# hand_rev_1_2_b.net
KiCad netlist of a schematic drawn in EAGLE
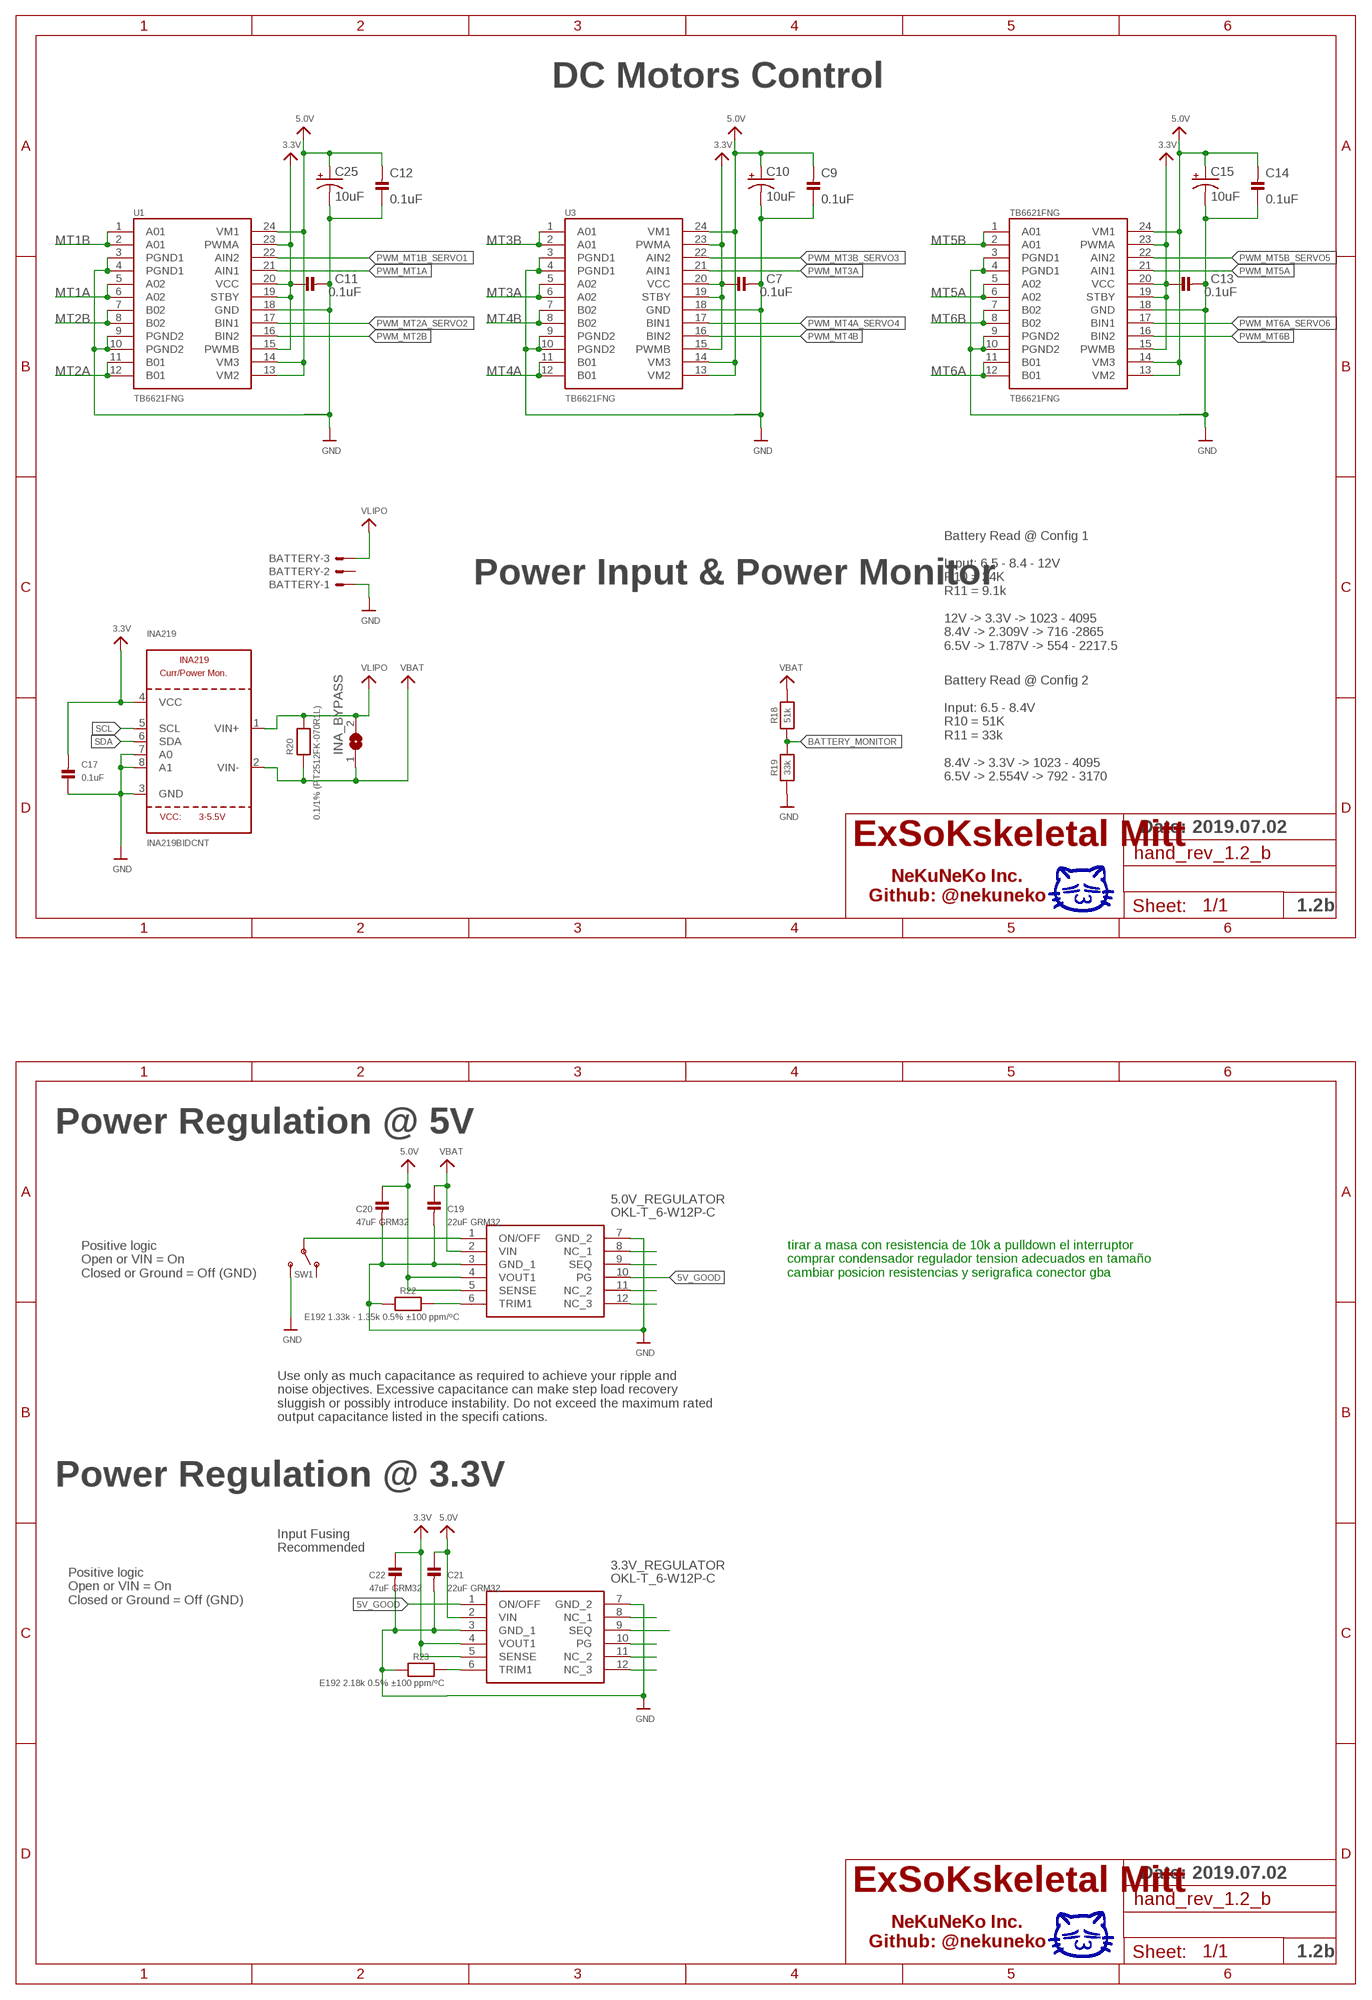
[diagram p0: schematic, sheet 1, part 1 of 2]
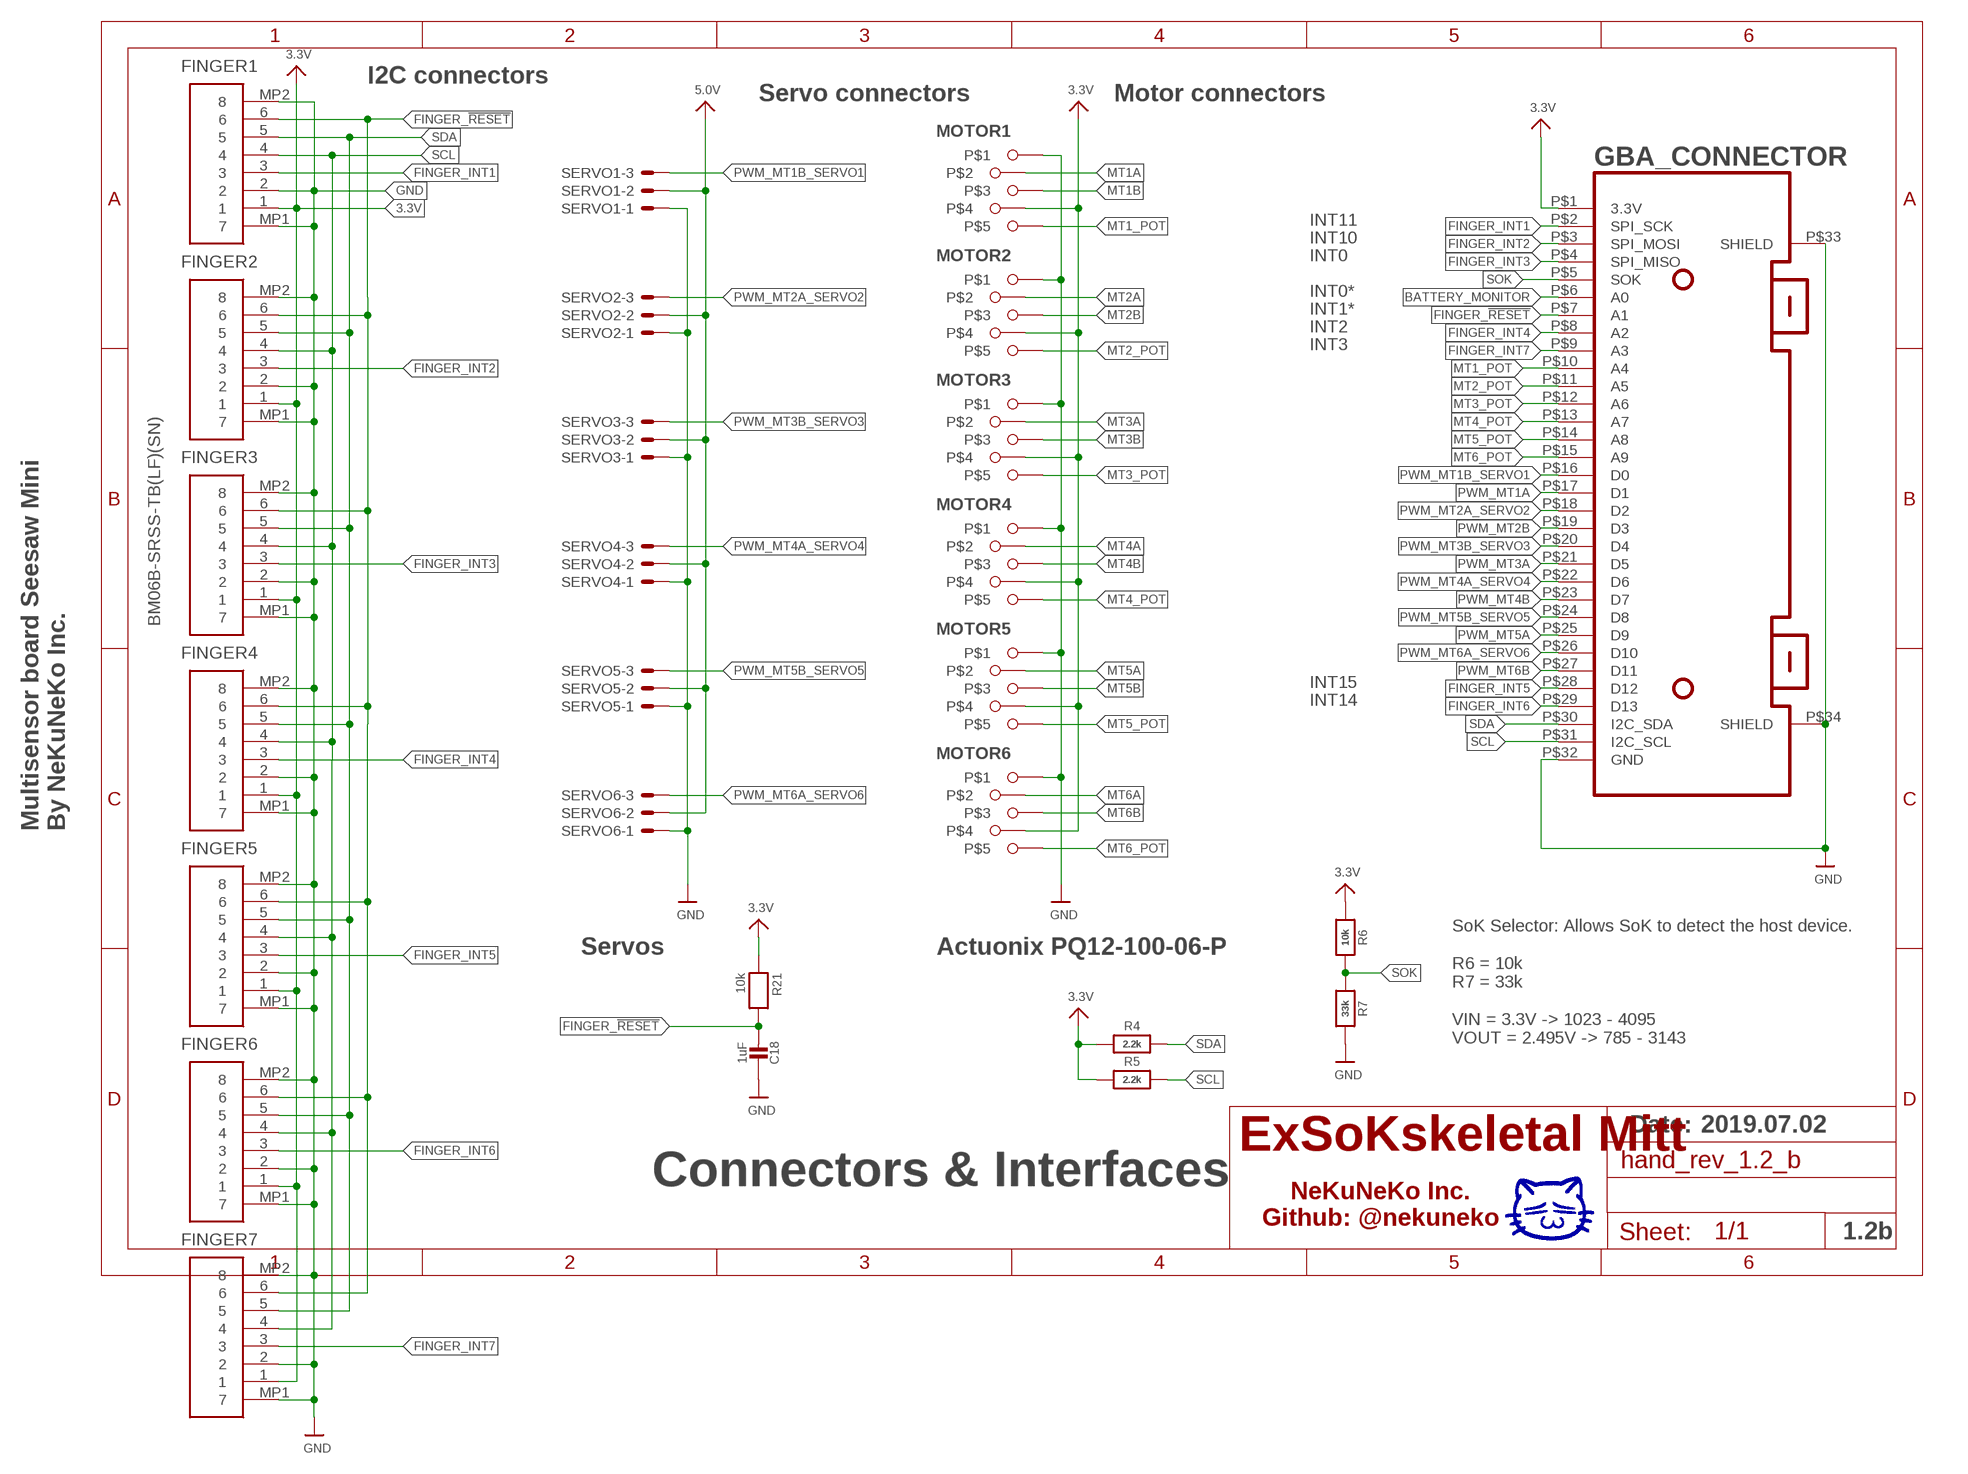
[diagram p1: schematic, sheet 1, part 2 of 2]

(export (version "E")
  (design (tool "Eeschema 10.0.6"))
  (components
    (comp (ref "3.3V_REGULATOR")
      (value "OKL-T_6-W12P-C")
      (footprint "eagle-import:OKL-T3-W12")
      (fields
        (field (name "MANUFACTURER_PART_NUMBER") "OKL-T/6-W12P-C")
        (field (name "MOUSER_PART_NUMBER") "580-OKL-T/6-W12P-C")
      )
      (libsource (lib "eagle-import") (part "OKL-T_6-W12P-C"))
    )
    (comp (ref "5.0V_REGULATOR")
      (value "OKL-T_6-W12P-C")
      (footprint "eagle-import:OKL-T3-W12")
      (fields
        (field (name "MANUFACTURER_PART_NUMBER") "OKL-T/6-W12P-C")
        (field (name "MOUSER_PART_NUMBER") "580-OKL-T/6-W12P-C")
      )
      (libsource (lib "eagle-import") (part "OKL-T_6-W12P-C"))
    )
    (comp (ref "BATTERY")
      (value "JST-XH-03-PIN-LONG-PAD")
      (footprint "eagle-import:JST-XH-03-PACKAGE-LONG-PAD")
      (libsource (lib "eagle-import") (part "JST-XH-03-PIN-LONG-PAD"))
    )
    (comp (ref "C7")
      (value "0.1uF")
      (footprint "eagle-import:_0603")
      (libsource (lib "eagle-import") (part "microbuilder_CAP_CERAMIC_0603"))
    )
    (comp (ref "C9")
      (value "0.1uF")
      (footprint "eagle-import:_0603")
      (libsource (lib "eagle-import") (part "microbuilder_CAP_CERAMIC_0603"))
    )
    (comp (ref "C10")
      (value "10uF")
      (footprint "eagle-import:0603-POLAR")
      (fields (field (name "MPN") "F981A106MMA"))
      (libsource (lib "eagle-import") (part "10UF-POLAR-0603-6.3V-20%(TANT)"))
    )
    (comp (ref "C11")
      (value "0.1uF")
      (footprint "eagle-import:_0603")
      (libsource (lib "eagle-import") (part "microbuilder_CAP_CERAMIC_0603"))
    )
    (comp (ref "C12")
      (value "0.1uF")
      (footprint "eagle-import:_0603")
      (libsource (lib "eagle-import") (part "microbuilder_CAP_CERAMIC_0603"))
    )
    (comp (ref "C13")
      (value "0.1uF")
      (footprint "eagle-import:_0603")
      (libsource (lib "eagle-import") (part "microbuilder_CAP_CERAMIC_0603"))
    )
    (comp (ref "C14")
      (value "0.1uF")
      (footprint "eagle-import:_0603")
      (libsource (lib "eagle-import") (part "microbuilder_CAP_CERAMIC_0603"))
    )
    (comp (ref "C15")
      (value "10uF")
      (footprint "eagle-import:0603-POLAR")
      (fields (field (name "MPN") "F981A106MMA"))
      (libsource (lib "eagle-import") (part "10UF-POLAR-0603-6.3V-20%(TANT)"))
    )
    (comp (ref "C17")
      (value "0.1uF")
      (footprint "eagle-import:_0603")
      (libsource (lib "eagle-import") (part "microbuilder_CAP_CERAMIC_0603"))
    )
    (comp (ref "C18")
      (value "1uF")
      (footprint "eagle-import:MICROBUILDER__0603")
      (libsource (lib "eagle-import") (part "CAP_CERAMIC_0603"))
    )
    (comp (ref "C19")
      (value "22uF GRM32")
      (footprint "eagle-import:1206")
      (libsource (lib "eagle-import") (part "CAP_CERAMIC1206"))
    )
    (comp (ref "C20")
      (value "47uF GRM32")
      (footprint "eagle-import:1206")
      (libsource (lib "eagle-import") (part "CAP_CERAMIC1206"))
    )
    (comp (ref "C21")
      (value "22uF GRM32")
      (footprint "eagle-import:1206")
      (libsource (lib "eagle-import") (part "CAP_CERAMIC1206"))
    )
    (comp (ref "C22")
      (value "47uF GRM32")
      (footprint "eagle-import:1206")
      (libsource (lib "eagle-import") (part "CAP_CERAMIC1206"))
    )
    (comp (ref "C25")
      (value "10uF")
      (footprint "eagle-import:0603-POLAR")
      (fields (field (name "MPN") "F981A106MMA"))
      (libsource (lib "eagle-import") (part "10UF-POLAR-0603-6.3V-20%(TANT)"))
    )
    (comp (ref "FINGER1")
      (value "BM06B-SRSS-TB(LF)(SN)")
      (footprint "eagle-import:BM06BSRSSTBLFSN")
      (fields (field (name "RS_PART_NUMBER") "5468782"))
      (libsource (lib "eagle-import") (part "BM06B-SRSS-TB(LF)(SN)"))
    )
    (comp (ref "FINGER2")
      (value "BM06B-SRSS-TB(LF)(SN)")
      (footprint "eagle-import:BM06BSRSSTBLFSN")
      (fields (field (name "RS_PART_NUMBER") "5468782"))
      (libsource (lib "eagle-import") (part "BM06B-SRSS-TB(LF)(SN)"))
    )
    (comp (ref "FINGER3")
      (value "BM06B-SRSS-TB(LF)(SN)")
      (footprint "eagle-import:BM06BSRSSTBLFSN")
      (fields (field (name "RS_PART_NUMBER") "5468782"))
      (libsource (lib "eagle-import") (part "BM06B-SRSS-TB(LF)(SN)"))
    )
    (comp (ref "FINGER4")
      (value "BM06B-SRSS-TB(LF)(SN)")
      (footprint "eagle-import:BM06BSRSSTBLFSN")
      (fields (field (name "RS_PART_NUMBER") "5468782"))
      (libsource (lib "eagle-import") (part "BM06B-SRSS-TB(LF)(SN)"))
    )
    (comp (ref "FINGER5")
      (value "BM06B-SRSS-TB(LF)(SN)")
      (footprint "eagle-import:BM06BSRSSTBLFSN")
      (fields (field (name "RS_PART_NUMBER") "5468782"))
      (libsource (lib "eagle-import") (part "BM06B-SRSS-TB(LF)(SN)"))
    )
    (comp (ref "FINGER6")
      (value "BM06B-SRSS-TB(LF)(SN)")
      (footprint "eagle-import:BM06BSRSSTBLFSN")
      (fields (field (name "RS_PART_NUMBER") "5468782"))
      (libsource (lib "eagle-import") (part "BM06B-SRSS-TB(LF)(SN)"))
    )
    (comp (ref "FINGER7")
      (value "BM06B-SRSS-TB(LF)(SN)")
      (footprint "eagle-import:BM06BSRSSTBLFSN")
      (fields (field (name "RS_PART_NUMBER") "5468782"))
      (libsource (lib "eagle-import") (part "BM06B-SRSS-TB(LF)(SN)"))
    )
    (comp (ref "GBA_CONNECTOR")
      (value "GBA_CARTRIDGEGBA_CARTRIDGE2")
      (footprint "eagle-import:GBA_CARTRIDGE2")
      (libsource (lib "eagle-import") (part "GBA_CARTRIDGEGBA_CARTRIDGE2"))
    )
    (comp (ref "INA219")
      (value "INA219BIDCNT")
      (footprint "eagle-import:SOT23-8")
      (libsource (lib "eagle-import") (part "INA219"))
    )
    (comp (ref "INA_BYPASS")
      (value "SOLDERJUMPERREFLOW_NOPASTE")
      (footprint "eagle-import:SOLDERJUMPER_REFLOW_NOPASTE")
      (libsource (lib "eagle-import") (part "SOLDERJUMPERREFLOW_NOPASTE"))
    )
    (comp (ref "MOTOR1")
      (value "Actuonix PQ12-100-06-P")
      (footprint "eagle-import:5PIN")
      (libsource (lib "eagle-import") (part "5PIN"))
    )
    (comp (ref "MOTOR2")
      (value "Actuonix PQ12-100-06-P")
      (footprint "eagle-import:5PIN")
      (libsource (lib "eagle-import") (part "5PIN"))
    )
    (comp (ref "MOTOR3")
      (value "Actuonix PQ12-100-06-P")
      (footprint "eagle-import:5PIN")
      (libsource (lib "eagle-import") (part "5PIN"))
    )
    (comp (ref "MOTOR4")
      (value "Actuonix PQ12-100-06-P")
      (footprint "eagle-import:5PIN")
      (libsource (lib "eagle-import") (part "5PIN"))
    )
    (comp (ref "MOTOR5")
      (value "Actuonix PQ12-100-06-P")
      (footprint "eagle-import:5PIN")
      (libsource (lib "eagle-import") (part "5PIN"))
    )
    (comp (ref "MOTOR6")
      (value "Actuonix PQ12-100-06-P")
      (footprint "eagle-import:5PIN")
      (libsource (lib "eagle-import") (part "5PIN"))
    )
    (comp (ref "R4")
      (value "2.2k")
      (footprint "eagle-import:_0603")
      (libsource (lib "eagle-import") (part "RESISTOR_0603"))
    )
    (comp (ref "R5")
      (value "2.2k")
      (footprint "eagle-import:_0603")
      (libsource (lib "eagle-import") (part "RESISTOR_0603"))
    )
    (comp (ref "R6")
      (value "10k")
      (footprint "eagle-import:_0603")
      (libsource (lib "eagle-import") (part "RESISTOR_0603"))
    )
    (comp (ref "R7")
      (value "33k")
      (footprint "eagle-import:_0603")
      (libsource (lib "eagle-import") (part "RESISTOR_0603"))
    )
    (comp (ref "R18")
      (value "51k")
      (footprint "eagle-import:_0603")
      (libsource (lib "eagle-import") (part "RESISTOR_0603"))
    )
    (comp (ref "R19")
      (value "33k")
      (footprint "eagle-import:_0603")
      (libsource (lib "eagle-import") (part "RESISTOR_0603"))
    )
    (comp (ref "R20")
      (value "0.1/1% (PT2512FK-070R1L)")
      (footprint "eagle-import:2512")
      (libsource (lib "eagle-import") (part "RESISTOR2512"))
    )
    (comp (ref "R21")
      (value "10k")
      (footprint "eagle-import:_0603")
      (libsource (lib "eagle-import") (part "RESISTOR_0603"))
    )
    (comp (ref "R22")
      (value "E192 1.33k - 1.35k 0.5% ±100 ppm/ºC")
      (footprint "eagle-import:_0603")
      (libsource (lib "eagle-import") (part "RESISTOR_0603"))
    )
    (comp (ref "R23")
      (value "E192 2.18k 0.5% ±100 ppm/ºC")
      (footprint "eagle-import:_0603")
      (libsource (lib "eagle-import") (part "RESISTOR_0603"))
    )
    (comp (ref "SERVO1")
      (value "JST-XH-03-PIN-LONG-PAD")
      (footprint "eagle-import:JST-XH-03-PACKAGE-LONG-PAD")
      (libsource (lib "eagle-import") (part "JST-XH-03-PIN-LONG-PAD"))
    )
    (comp (ref "SERVO2")
      (value "JST-XH-03-PIN-LONG-PAD")
      (footprint "eagle-import:JST-XH-03-PACKAGE-LONG-PAD")
      (libsource (lib "eagle-import") (part "JST-XH-03-PIN-LONG-PAD"))
    )
    (comp (ref "SERVO3")
      (value "JST-XH-03-PIN-LONG-PAD")
      (footprint "eagle-import:JST-XH-03-PACKAGE-LONG-PAD")
      (libsource (lib "eagle-import") (part "JST-XH-03-PIN-LONG-PAD"))
    )
    (comp (ref "SERVO4")
      (value "JST-XH-03-PIN-LONG-PAD")
      (footprint "eagle-import:JST-XH-03-PACKAGE-LONG-PAD")
      (libsource (lib "eagle-import") (part "JST-XH-03-PIN-LONG-PAD"))
    )
    (comp (ref "SERVO5")
      (value "JST-XH-03-PIN-LONG-PAD")
      (footprint "eagle-import:JST-XH-03-PACKAGE-LONG-PAD")
      (libsource (lib "eagle-import") (part "JST-XH-03-PIN-LONG-PAD"))
    )
    (comp (ref "SERVO6")
      (value "JST-XH-03-PIN-LONG-PAD")
      (footprint "eagle-import:JST-XH-03-PACKAGE-LONG-PAD")
      (libsource (lib "eagle-import") (part "JST-XH-03-PIN-LONG-PAD"))
    )
    (comp (ref "SW1")
      (value "SWITCH_SPDT")
      (footprint "eagle-import:SPDT_SMT_SSSS811101")
      (libsource (lib "eagle-import") (part "SWITCH_SPDT"))
    )
    (comp (ref "TB6621FNG")
      (value "TB6621FNG")
      (footprint "eagle-import:SSOP24")
      (libsource (lib "eagle-import") (part "TB6621FNG"))
    )
    (comp (ref "U1")
      (value "TB6621FNG")
      (footprint "eagle-import:SSOP24")
      (libsource (lib "eagle-import") (part "TB6621FNG"))
    )
    (comp (ref "U3")
      (value "TB6621FNG")
      (footprint "eagle-import:SSOP24")
      (libsource (lib "eagle-import") (part "TB6621FNG"))
    )
  )
  (nets
    (net (code "1") (name "/FINGER_~{RESET}") (class "Default")
      (node (ref "C18") (pin "2") (pinfunction "2_2") (pintype "passive"))
      (node (ref "FINGER1") (pin "6") (pinfunction "6_6") (pintype "bidirectional"))
      (node (ref "FINGER2") (pin "6") (pinfunction "6_6") (pintype "bidirectional"))
      (node (ref "FINGER3") (pin "6") (pinfunction "6_6") (pintype "bidirectional"))
      (node (ref "FINGER4") (pin "6") (pinfunction "6_6") (pintype "bidirectional"))
      (node (ref "FINGER5") (pin "6") (pinfunction "6_6") (pintype "bidirectional"))
      (node (ref "FINGER6") (pin "6") (pinfunction "6_6") (pintype "bidirectional"))
      (node (ref "FINGER7") (pin "6") (pinfunction "6_6") (pintype "bidirectional"))
      (node (ref "GBA_CONNECTOR") (pin "P$7") (pinfunction "A1_P$7") (pintype "bidirectional"))
      (node (ref "R21") (pin "2") (pinfunction "2_2") (pintype "passive"))
    )
    (net (code "2") (name "3.3V") (class "Default")
      (node (ref "3.3V_REGULATOR") (pin "4") (pinfunction "VOUT1_4") (pintype "bidirectional"))
      (node (ref "3.3V_REGULATOR") (pin "5") (pinfunction "SENSE_5") (pintype "bidirectional"))
      (node (ref "C11") (pin "1") (pinfunction "P$1_1") (pintype "passive"))
      (node (ref "C13") (pin "1") (pinfunction "P$1_1") (pintype "passive"))
      (node (ref "C17") (pin "2") (pinfunction "P$2_2") (pintype "passive"))
      (node (ref "C22") (pin "1") (pinfunction "P$1_1") (pintype "passive"))
      (node (ref "C7") (pin "1") (pinfunction "P$1_1") (pintype "passive"))
      (node (ref "FINGER1") (pin "1") (pinfunction "1_1") (pintype "bidirectional"))
      (node (ref "FINGER2") (pin "1") (pinfunction "1_1") (pintype "bidirectional"))
      (node (ref "FINGER3") (pin "1") (pinfunction "1_1") (pintype "bidirectional"))
      (node (ref "FINGER4") (pin "1") (pinfunction "1_1") (pintype "bidirectional"))
      (node (ref "FINGER5") (pin "1") (pinfunction "1_1") (pintype "bidirectional"))
      (node (ref "FINGER6") (pin "1") (pinfunction "1_1") (pintype "bidirectional"))
      (node (ref "FINGER7") (pin "1") (pinfunction "1_1") (pintype "bidirectional"))
      (node (ref "GBA_CONNECTOR") (pin "P$1") (pinfunction "3.3V_P$1") (pintype "power_in"))
      (node (ref "INA219") (pin "4") (pinfunction "VCC_4") (pintype "bidirectional"))
      (node (ref "MOTOR1") (pin "4") (pinfunction "P$4_4") (pintype "bidirectional"))
      (node (ref "MOTOR2") (pin "4") (pinfunction "P$4_4") (pintype "bidirectional"))
      (node (ref "MOTOR3") (pin "4") (pinfunction "P$4_4") (pintype "bidirectional"))
      (node (ref "MOTOR4") (pin "4") (pinfunction "P$4_4") (pintype "bidirectional"))
      (node (ref "MOTOR5") (pin "4") (pinfunction "P$4_4") (pintype "bidirectional"))
      (node (ref "MOTOR6") (pin "4") (pinfunction "P$4_4") (pintype "bidirectional"))
      (node (ref "R21") (pin "1") (pinfunction "1_1") (pintype "passive"))
      (node (ref "R4") (pin "1") (pinfunction "1_1") (pintype "passive"))
      (node (ref "R5") (pin "1") (pinfunction "1_1") (pintype "passive"))
      (node (ref "R6") (pin "1") (pinfunction "1_1") (pintype "passive"))
      (node (ref "TB6621FNG") (pin "15") (pinfunction "PWMB_15") (pintype "bidirectional"))
      (node (ref "TB6621FNG") (pin "19") (pinfunction "STBY_19") (pintype "bidirectional"))
      (node (ref "TB6621FNG") (pin "20") (pinfunction "VCC_20") (pintype "bidirectional"))
      (node (ref "TB6621FNG") (pin "23") (pinfunction "PWMA_23") (pintype "bidirectional"))
      (node (ref "U1") (pin "15") (pinfunction "PWMB_15") (pintype "bidirectional"))
      (node (ref "U1") (pin "19") (pinfunction "STBY_19") (pintype "bidirectional"))
      (node (ref "U1") (pin "20") (pinfunction "VCC_20") (pintype "bidirectional"))
      (node (ref "U1") (pin "23") (pinfunction "PWMA_23") (pintype "bidirectional"))
      (node (ref "U3") (pin "15") (pinfunction "PWMB_15") (pintype "bidirectional"))
      (node (ref "U3") (pin "19") (pinfunction "STBY_19") (pintype "bidirectional"))
      (node (ref "U3") (pin "20") (pinfunction "VCC_20") (pintype "bidirectional"))
      (node (ref "U3") (pin "23") (pinfunction "PWMA_23") (pintype "bidirectional"))
    )
    (net (code "3") (name "5.0V") (class "Default")
      (node (ref "3.3V_REGULATOR") (pin "2") (pinfunction "VIN_2") (pintype "bidirectional"))
      (node (ref "5.0V_REGULATOR") (pin "4") (pinfunction "VOUT1_4") (pintype "bidirectional"))
      (node (ref "5.0V_REGULATOR") (pin "5") (pinfunction "SENSE_5") (pintype "bidirectional"))
      (node (ref "C10") (pin "+") (pinfunction "+_+") (pintype "passive"))
      (node (ref "C12") (pin "2") (pinfunction "P$2_2") (pintype "passive"))
      (node (ref "C14") (pin "2") (pinfunction "P$2_2") (pintype "passive"))
      (node (ref "C15") (pin "+") (pinfunction "+_+") (pintype "passive"))
      (node (ref "C20") (pin "1") (pinfunction "P$1_1") (pintype "passive"))
      (node (ref "C21") (pin "1") (pinfunction "P$1_1") (pintype "passive"))
      (node (ref "C25") (pin "+") (pinfunction "+_+") (pintype "passive"))
      (node (ref "C9") (pin "2") (pinfunction "P$2_2") (pintype "passive"))
      (node (ref "SERVO1") (pin "2") (pinfunction "S_2") (pintype "passive"))
      (node (ref "SERVO2") (pin "2") (pinfunction "S_2") (pintype "passive"))
      (node (ref "SERVO3") (pin "2") (pinfunction "S_2") (pintype "passive"))
      (node (ref "SERVO4") (pin "2") (pinfunction "S_2") (pintype "passive"))
      (node (ref "SERVO5") (pin "2") (pinfunction "S_2") (pintype "passive"))
      (node (ref "SERVO6") (pin "2") (pinfunction "S_2") (pintype "passive"))
      (node (ref "TB6621FNG") (pin "13") (pinfunction "VM2_13") (pintype "bidirectional"))
      (node (ref "TB6621FNG") (pin "14") (pinfunction "VM3_14") (pintype "bidirectional"))
      (node (ref "TB6621FNG") (pin "24") (pinfunction "VM1_24") (pintype "bidirectional"))
      (node (ref "U1") (pin "13") (pinfunction "VM2_13") (pintype "bidirectional"))
      (node (ref "U1") (pin "14") (pinfunction "VM3_14") (pintype "bidirectional"))
      (node (ref "U1") (pin "24") (pinfunction "VM1_24") (pintype "bidirectional"))
      (node (ref "U3") (pin "13") (pinfunction "VM2_13") (pintype "bidirectional"))
      (node (ref "U3") (pin "14") (pinfunction "VM3_14") (pintype "bidirectional"))
      (node (ref "U3") (pin "24") (pinfunction "VM1_24") (pintype "bidirectional"))
    )
    (net (code "4") (name "5V_GOOD") (class "Default")
      (node (ref "3.3V_REGULATOR") (pin "1") (pinfunction "ON/OFF_1") (pintype "bidirectional"))
      (node (ref "5.0V_REGULATOR") (pin "10") (pinfunction "PG_10") (pintype "bidirectional"))
    )
    (net (code "5") (name "BATTERY_MONITOR") (class "Default")
      (node (ref "GBA_CONNECTOR") (pin "P$6") (pinfunction "A0_P$6") (pintype "bidirectional"))
      (node (ref "R18") (pin "1") (pinfunction "1_1") (pintype "passive"))
      (node (ref "R19") (pin "2") (pinfunction "2_2") (pintype "passive"))
    )
    (net (code "6") (name "FINGER_INT1") (class "Default")
      (node (ref "FINGER1") (pin "3") (pinfunction "3_3") (pintype "bidirectional"))
      (node (ref "GBA_CONNECTOR") (pin "P$2") (pinfunction "SPI_SCK_P$2") (pintype "bidirectional"))
    )
    (net (code "7") (name "FINGER_INT2") (class "Default")
      (node (ref "FINGER2") (pin "3") (pinfunction "3_3") (pintype "bidirectional"))
      (node (ref "GBA_CONNECTOR") (pin "P$3") (pinfunction "SPI_MOSI_P$3") (pintype "bidirectional"))
    )
    (net (code "8") (name "FINGER_INT3") (class "Default")
      (node (ref "FINGER3") (pin "3") (pinfunction "3_3") (pintype "bidirectional"))
      (node (ref "GBA_CONNECTOR") (pin "P$4") (pinfunction "SPI_MISO_P$4") (pintype "bidirectional"))
    )
    (net (code "9") (name "FINGER_INT4") (class "Default")
      (node (ref "FINGER4") (pin "3") (pinfunction "3_3") (pintype "bidirectional"))
      (node (ref "GBA_CONNECTOR") (pin "P$8") (pinfunction "A2_P$8") (pintype "bidirectional"))
    )
    (net (code "10") (name "FINGER_INT5") (class "Default")
      (node (ref "FINGER5") (pin "3") (pinfunction "3_3") (pintype "bidirectional"))
      (node (ref "GBA_CONNECTOR") (pin "P$28") (pinfunction "D12_P$28") (pintype "bidirectional"))
    )
    (net (code "11") (name "FINGER_INT6") (class "Default")
      (node (ref "FINGER6") (pin "3") (pinfunction "3_3") (pintype "bidirectional"))
      (node (ref "GBA_CONNECTOR") (pin "P$29") (pinfunction "D13_P$29") (pintype "bidirectional"))
    )
    (net (code "12") (name "FINGER_INT7") (class "Default")
      (node (ref "FINGER7") (pin "3") (pinfunction "3_3") (pintype "bidirectional"))
      (node (ref "GBA_CONNECTOR") (pin "P$9") (pinfunction "A3_P$9") (pintype "bidirectional"))
    )
    (net (code "13") (name "GND") (class "Default")
      (node (ref "3.3V_REGULATOR") (pin "3") (pinfunction "GND_1_3") (pintype "bidirectional"))
      (node (ref "3.3V_REGULATOR") (pin "7") (pinfunction "GND_2_7") (pintype "bidirectional"))
      (node (ref "5.0V_REGULATOR") (pin "3") (pinfunction "GND_1_3") (pintype "bidirectional"))
      (node (ref "5.0V_REGULATOR") (pin "7") (pinfunction "GND_2_7") (pintype "bidirectional"))
      (node (ref "BATTERY") (pin "1") (pinfunction "S_1") (pintype "passive"))
      (node (ref "C10") (pin "-") (pinfunction "-_-") (pintype "passive"))
      (node (ref "C11") (pin "2") (pinfunction "P$2_2") (pintype "passive"))
      (node (ref "C12") (pin "1") (pinfunction "P$1_1") (pintype "passive"))
      (node (ref "C13") (pin "2") (pinfunction "P$2_2") (pintype "passive"))
      (node (ref "C14") (pin "1") (pinfunction "P$1_1") (pintype "passive"))
      (node (ref "C15") (pin "-") (pinfunction "-_-") (pintype "passive"))
      (node (ref "C17") (pin "1") (pinfunction "P$1_1") (pintype "passive"))
      (node (ref "C18") (pin "1") (pinfunction "1_1") (pintype "passive"))
      (node (ref "C19") (pin "2") (pinfunction "P$2_2") (pintype "passive"))
      (node (ref "C20") (pin "2") (pinfunction "P$2_2") (pintype "passive"))
      (node (ref "C21") (pin "2") (pinfunction "P$2_2") (pintype "passive"))
      (node (ref "C22") (pin "2") (pinfunction "P$2_2") (pintype "passive"))
      (node (ref "C25") (pin "-") (pinfunction "-_-") (pintype "passive"))
      (node (ref "C7") (pin "2") (pinfunction "P$2_2") (pintype "passive"))
      (node (ref "C9") (pin "1") (pinfunction "P$1_1") (pintype "passive"))
      (node (ref "FINGER1") (pin "2") (pinfunction "2_2") (pintype "bidirectional"))
      (node (ref "FINGER1") (pin "MP1") (pinfunction "7_MP1") (pintype "bidirectional"))
      (node (ref "FINGER1") (pin "MP2") (pinfunction "8_MP2") (pintype "bidirectional"))
      (node (ref "FINGER2") (pin "2") (pinfunction "2_2") (pintype "bidirectional"))
      (node (ref "FINGER2") (pin "MP1") (pinfunction "7_MP1") (pintype "bidirectional"))
      (node (ref "FINGER2") (pin "MP2") (pinfunction "8_MP2") (pintype "bidirectional"))
      (node (ref "FINGER3") (pin "2") (pinfunction "2_2") (pintype "bidirectional"))
      (node (ref "FINGER3") (pin "MP1") (pinfunction "7_MP1") (pintype "bidirectional"))
      (node (ref "FINGER3") (pin "MP2") (pinfunction "8_MP2") (pintype "bidirectional"))
      (node (ref "FINGER4") (pin "2") (pinfunction "2_2") (pintype "bidirectional"))
      (node (ref "FINGER4") (pin "MP1") (pinfunction "7_MP1") (pintype "bidirectional"))
      (node (ref "FINGER4") (pin "MP2") (pinfunction "8_MP2") (pintype "bidirectional"))
      (node (ref "FINGER5") (pin "2") (pinfunction "2_2") (pintype "bidirectional"))
      (node (ref "FINGER5") (pin "MP1") (pinfunction "7_MP1") (pintype "bidirectional"))
      (node (ref "FINGER5") (pin "MP2") (pinfunction "8_MP2") (pintype "bidirectional"))
      (node (ref "FINGER6") (pin "2") (pinfunction "2_2") (pintype "bidirectional"))
      (node (ref "FINGER6") (pin "MP1") (pinfunction "7_MP1") (pintype "bidirectional"))
      (node (ref "FINGER6") (pin "MP2") (pinfunction "8_MP2") (pintype "bidirectional"))
      (node (ref "FINGER7") (pin "2") (pinfunction "2_2") (pintype "bidirectional"))
      (node (ref "FINGER7") (pin "MP1") (pinfunction "7_MP1") (pintype "bidirectional"))
      (node (ref "FINGER7") (pin "MP2") (pinfunction "8_MP2") (pintype "bidirectional"))
      (node (ref "GBA_CONNECTOR") (pin "P$32") (pinfunction "GND_P$32") (pintype "power_in"))
      (node (ref "GBA_CONNECTOR") (pin "P$33") (pinfunction "SHIELD_P$33") (pintype "bidirectional"))
      (node (ref "GBA_CONNECTOR") (pin "P$34") (pinfunction "SHIELD_P$34") (pintype "bidirectional"))
      (node (ref "INA219") (pin "3") (pinfunction "GND_3") (pintype "bidirectional"))
      (node (ref "INA219") (pin "7") (pinfunction "A0_7") (pintype "bidirectional"))
      (node (ref "INA219") (pin "8") (pinfunction "A1_8") (pintype "bidirectional"))
      (node (ref "MOTOR1") (pin "1") (pinfunction "P$1_1") (pintype "bidirectional"))
      (node (ref "MOTOR2") (pin "1") (pinfunction "P$1_1") (pintype "bidirectional"))
      (node (ref "MOTOR3") (pin "1") (pinfunction "P$1_1") (pintype "bidirectional"))
      (node (ref "MOTOR4") (pin "1") (pinfunction "P$1_1") (pintype "bidirectional"))
      (node (ref "MOTOR5") (pin "1") (pinfunction "P$1_1") (pintype "bidirectional"))
      (node (ref "MOTOR6") (pin "1") (pinfunction "P$1_1") (pintype "bidirectional"))
      (node (ref "R19") (pin "1") (pinfunction "1_1") (pintype "passive"))
      (node (ref "R22") (pin "2") (pinfunction "2_2") (pintype "passive"))
      (node (ref "R23") (pin "2") (pinfunction "2_2") (pintype "passive"))
      (node (ref "R7") (pin "2") (pinfunction "2_2") (pintype "passive"))
      (node (ref "SERVO1") (pin "1") (pinfunction "S_1") (pintype "passive"))
      (node (ref "SERVO2") (pin "1") (pinfunction "S_1") (pintype "passive"))
      (node (ref "SERVO3") (pin "1") (pinfunction "S_1") (pintype "passive"))
      (node (ref "SERVO4") (pin "1") (pinfunction "S_1") (pintype "passive"))
      (node (ref "SERVO5") (pin "1") (pinfunction "S_1") (pintype "passive"))
      (node (ref "SERVO6") (pin "1") (pinfunction "S_1") (pintype "passive"))
      (node (ref "SW1") (pin "C") (pinfunction "S_C") (pintype "passive"))
      (node (ref "TB6621FNG") (pin "10") (pinfunction "PGND2_10") (pintype "bidirectional"))
      (node (ref "TB6621FNG") (pin "18") (pinfunction "GND_18") (pintype "bidirectional"))
      (node (ref "TB6621FNG") (pin "3") (pinfunction "PGND1_3") (pintype "bidirectional"))
      (node (ref "TB6621FNG") (pin "4") (pinfunction "PGND1_4") (pintype "bidirectional"))
      (node (ref "TB6621FNG") (pin "9") (pinfunction "PGND2_9") (pintype "bidirectional"))
      (node (ref "U1") (pin "10") (pinfunction "PGND2_10") (pintype "bidirectional"))
      (node (ref "U1") (pin "18") (pinfunction "GND_18") (pintype "bidirectional"))
      (node (ref "U1") (pin "3") (pinfunction "PGND1_3") (pintype "bidirectional"))
      (node (ref "U1") (pin "4") (pinfunction "PGND1_4") (pintype "bidirectional"))
      (node (ref "U1") (pin "9") (pinfunction "PGND2_9") (pintype "bidirectional"))
      (node (ref "U3") (pin "10") (pinfunction "PGND2_10") (pintype "bidirectional"))
      (node (ref "U3") (pin "18") (pinfunction "GND_18") (pintype "bidirectional"))
      (node (ref "U3") (pin "3") (pinfunction "PGND1_3") (pintype "bidirectional"))
      (node (ref "U3") (pin "4") (pinfunction "PGND1_4") (pintype "bidirectional"))
      (node (ref "U3") (pin "9") (pinfunction "PGND2_9") (pintype "bidirectional"))
    )
    (net (code "14") (name "MT1A") (class "Default")
      (node (ref "MOTOR1") (pin "2") (pinfunction "P$2_2") (pintype "bidirectional"))
      (node (ref "U1") (pin "5") (pinfunction "A02_5") (pintype "bidirectional"))
      (node (ref "U1") (pin "6") (pinfunction "A02_6") (pintype "bidirectional"))
    )
    (net (code "15") (name "MT1B") (class "Default")
      (node (ref "MOTOR1") (pin "3") (pinfunction "P$3_3") (pintype "bidirectional"))
      (node (ref "U1") (pin "1") (pinfunction "A01_1") (pintype "bidirectional"))
      (node (ref "U1") (pin "2") (pinfunction "A01_2") (pintype "bidirectional"))
    )
    (net (code "16") (name "MT1_POT") (class "Default")
      (node (ref "GBA_CONNECTOR") (pin "P$10") (pinfunction "A4_P$10") (pintype "bidirectional"))
      (node (ref "MOTOR1") (pin "5") (pinfunction "P$5_5") (pintype "bidirectional"))
    )
    (net (code "17") (name "MT2A") (class "Default")
      (node (ref "MOTOR2") (pin "2") (pinfunction "P$2_2") (pintype "bidirectional"))
      (node (ref "U1") (pin "11") (pinfunction "B01_11") (pintype "bidirectional"))
      (node (ref "U1") (pin "12") (pinfunction "B01_12") (pintype "bidirectional"))
    )
    (net (code "18") (name "MT2B") (class "Default")
      (node (ref "MOTOR2") (pin "3") (pinfunction "P$3_3") (pintype "bidirectional"))
      (node (ref "U1") (pin "7") (pinfunction "B02_7") (pintype "bidirectional"))
      (node (ref "U1") (pin "8") (pinfunction "B02_8") (pintype "bidirectional"))
    )
    (net (code "19") (name "MT2_POT") (class "Default")
      (node (ref "GBA_CONNECTOR") (pin "P$11") (pinfunction "A5_P$11") (pintype "bidirectional"))
      (node (ref "MOTOR2") (pin "5") (pinfunction "P$5_5") (pintype "bidirectional"))
    )
    (net (code "20") (name "MT3A") (class "Default")
      (node (ref "MOTOR3") (pin "2") (pinfunction "P$2_2") (pintype "bidirectional"))
      (node (ref "U3") (pin "5") (pinfunction "A02_5") (pintype "bidirectional"))
      (node (ref "U3") (pin "6") (pinfunction "A02_6") (pintype "bidirectional"))
    )
    (net (code "21") (name "MT3B") (class "Default")
      (node (ref "MOTOR3") (pin "3") (pinfunction "P$3_3") (pintype "bidirectional"))
      (node (ref "U3") (pin "1") (pinfunction "A01_1") (pintype "bidirectional"))
      (node (ref "U3") (pin "2") (pinfunction "A01_2") (pintype "bidirectional"))
    )
    (net (code "22") (name "MT3_POT") (class "Default")
      (node (ref "GBA_CONNECTOR") (pin "P$12") (pinfunction "A6_P$12") (pintype "bidirectional"))
      (node (ref "MOTOR3") (pin "5") (pinfunction "P$5_5") (pintype "bidirectional"))
    )
    (net (code "23") (name "MT4A") (class "Default")
      (node (ref "MOTOR4") (pin "2") (pinfunction "P$2_2") (pintype "bidirectional"))
      (node (ref "U3") (pin "11") (pinfunction "B01_11") (pintype "bidirectional"))
      (node (ref "U3") (pin "12") (pinfunction "B01_12") (pintype "bidirectional"))
    )
    (net (code "24") (name "MT4B") (class "Default")
      (node (ref "MOTOR4") (pin "3") (pinfunction "P$3_3") (pintype "bidirectional"))
      (node (ref "U3") (pin "7") (pinfunction "B02_7") (pintype "bidirectional"))
      (node (ref "U3") (pin "8") (pinfunction "B02_8") (pintype "bidirectional"))
    )
    (net (code "25") (name "MT4_POT") (class "Default")
      (node (ref "GBA_CONNECTOR") (pin "P$13") (pinfunction "A7_P$13") (pintype "bidirectional"))
      (node (ref "MOTOR4") (pin "5") (pinfunction "P$5_5") (pintype "bidirectional"))
    )
    (net (code "26") (name "MT5A") (class "Default")
      (node (ref "MOTOR5") (pin "2") (pinfunction "P$2_2") (pintype "bidirectional"))
      (node (ref "TB6621FNG") (pin "5") (pinfunction "A02_5") (pintype "bidirectional"))
      (node (ref "TB6621FNG") (pin "6") (pinfunction "A02_6") (pintype "bidirectional"))
    )
    (net (code "27") (name "MT5B") (class "Default")
      (node (ref "MOTOR5") (pin "3") (pinfunction "P$3_3") (pintype "bidirectional"))
      (node (ref "TB6621FNG") (pin "1") (pinfunction "A01_1") (pintype "bidirectional"))
      (node (ref "TB6621FNG") (pin "2") (pinfunction "A01_2") (pintype "bidirectional"))
    )
    (net (code "28") (name "MT5_POT") (class "Default")
      (node (ref "GBA_CONNECTOR") (pin "P$14") (pinfunction "A8_P$14") (pintype "bidirectional"))
      (node (ref "MOTOR5") (pin "5") (pinfunction "P$5_5") (pintype "bidirectional"))
    )
    (net (code "29") (name "MT6A") (class "Default")
      (node (ref "MOTOR6") (pin "2") (pinfunction "P$2_2") (pintype "bidirectional"))
      (node (ref "TB6621FNG") (pin "11") (pinfunction "B01_11") (pintype "bidirectional"))
      (node (ref "TB6621FNG") (pin "12") (pinfunction "B01_12") (pintype "bidirectional"))
    )
    (net (code "30") (name "MT6B") (class "Default")
      (node (ref "MOTOR6") (pin "3") (pinfunction "P$3_3") (pintype "bidirectional"))
      (node (ref "TB6621FNG") (pin "7") (pinfunction "B02_7") (pintype "bidirectional"))
      (node (ref "TB6621FNG") (pin "8") (pinfunction "B02_8") (pintype "bidirectional"))
    )
    (net (code "31") (name "MT6_POT") (class "Default")
      (node (ref "GBA_CONNECTOR") (pin "P$15") (pinfunction "A9_P$15") (pintype "bidirectional"))
      (node (ref "MOTOR6") (pin "5") (pinfunction "P$5_5") (pintype "bidirectional"))
    )
    (net (code "32") (name "Net-(3.3V_REGULATOR-TRIM1)") (class "Default")
      (node (ref "3.3V_REGULATOR") (pin "6") (pinfunction "TRIM1_6") (pintype "bidirectional"))
      (node (ref "R23") (pin "1") (pinfunction "1_1") (pintype "passive"))
    )
    (net (code "33") (name "Net-(5.0V_REGULATOR-ON{slash}OFF)") (class "Default")
      (node (ref "5.0V_REGULATOR") (pin "1") (pinfunction "ON/OFF_1") (pintype "bidirectional"))
      (node (ref "SW1") (pin "B") (pinfunction "P_B") (pintype "passive"))
    )
    (net (code "34") (name "Net-(5.0V_REGULATOR-TRIM1)") (class "Default")
      (node (ref "5.0V_REGULATOR") (pin "6") (pinfunction "TRIM1_6") (pintype "bidirectional"))
      (node (ref "R22") (pin "1") (pinfunction "1_1") (pintype "passive"))
    )
    (net (code "35") (name "PWM_MT1A") (class "Default")
      (node (ref "GBA_CONNECTOR") (pin "P$17") (pinfunction "D1_P$17") (pintype "bidirectional"))
      (node (ref "U1") (pin "21") (pinfunction "AIN1_21") (pintype "bidirectional"))
    )
    (net (code "36") (name "PWM_MT1B_SERVO1") (class "Default")
      (node (ref "GBA_CONNECTOR") (pin "P$16") (pinfunction "D0_P$16") (pintype "bidirectional"))
      (node (ref "SERVO1") (pin "3") (pinfunction "S_3") (pintype "passive"))
      (node (ref "U1") (pin "22") (pinfunction "AIN2_22") (pintype "bidirectional"))
    )
    (net (code "37") (name "PWM_MT2A_SERVO2") (class "Default")
      (node (ref "GBA_CONNECTOR") (pin "P$18") (pinfunction "D2_P$18") (pintype "bidirectional"))
      (node (ref "SERVO2") (pin "3") (pinfunction "S_3") (pintype "passive"))
      (node (ref "U1") (pin "17") (pinfunction "BIN1_17") (pintype "bidirectional"))
    )
    (net (code "38") (name "PWM_MT2B") (class "Default")
      (node (ref "GBA_CONNECTOR") (pin "P$19") (pinfunction "D3_P$19") (pintype "bidirectional"))
      (node (ref "U1") (pin "16") (pinfunction "BIN2_16") (pintype "bidirectional"))
    )
    (net (code "39") (name "PWM_MT3A") (class "Default")
      (node (ref "GBA_CONNECTOR") (pin "P$21") (pinfunction "D5_P$21") (pintype "bidirectional"))
      (node (ref "U3") (pin "21") (pinfunction "AIN1_21") (pintype "bidirectional"))
    )
    (net (code "40") (name "PWM_MT3B_SERVO3") (class "Default")
      (node (ref "GBA_CONNECTOR") (pin "P$20") (pinfunction "D4_P$20") (pintype "bidirectional"))
      (node (ref "SERVO3") (pin "3") (pinfunction "S_3") (pintype "passive"))
      (node (ref "U3") (pin "22") (pinfunction "AIN2_22") (pintype "bidirectional"))
    )
    (net (code "41") (name "PWM_MT4A_SERVO4") (class "Default")
      (node (ref "GBA_CONNECTOR") (pin "P$22") (pinfunction "D6_P$22") (pintype "bidirectional"))
      (node (ref "SERVO4") (pin "3") (pinfunction "S_3") (pintype "passive"))
      (node (ref "U3") (pin "17") (pinfunction "BIN1_17") (pintype "bidirectional"))
    )
    (net (code "42") (name "PWM_MT4B") (class "Default")
      (node (ref "GBA_CONNECTOR") (pin "P$23") (pinfunction "D7_P$23") (pintype "bidirectional"))
      (node (ref "U3") (pin "16") (pinfunction "BIN2_16") (pintype "bidirectional"))
    )
    (net (code "43") (name "PWM_MT5A") (class "Default")
      (node (ref "GBA_CONNECTOR") (pin "P$25") (pinfunction "D9_P$25") (pintype "bidirectional"))
      (node (ref "TB6621FNG") (pin "21") (pinfunction "AIN1_21") (pintype "bidirectional"))
    )
    (net (code "44") (name "PWM_MT5B_SERVO5") (class "Default")
      (node (ref "GBA_CONNECTOR") (pin "P$24") (pinfunction "D8_P$24") (pintype "bidirectional"))
      (node (ref "SERVO5") (pin "3") (pinfunction "S_3") (pintype "passive"))
      (node (ref "TB6621FNG") (pin "22") (pinfunction "AIN2_22") (pintype "bidirectional"))
    )
    (net (code "45") (name "PWM_MT6A_SERVO6") (class "Default")
      (node (ref "GBA_CONNECTOR") (pin "P$26") (pinfunction "D10_P$26") (pintype "bidirectional"))
      (node (ref "SERVO6") (pin "3") (pinfunction "S_3") (pintype "passive"))
      (node (ref "TB6621FNG") (pin "17") (pinfunction "BIN1_17") (pintype "bidirectional"))
    )
    (net (code "46") (name "PWM_MT6B") (class "Default")
      (node (ref "GBA_CONNECTOR") (pin "P$27") (pinfunction "D11_P$27") (pintype "bidirectional"))
      (node (ref "TB6621FNG") (pin "16") (pinfunction "BIN2_16") (pintype "bidirectional"))
    )
    (net (code "47") (name "SCL") (class "Default")
      (node (ref "FINGER1") (pin "4") (pinfunction "4_4") (pintype "bidirectional"))
      (node (ref "FINGER2") (pin "4") (pinfunction "4_4") (pintype "bidirectional"))
      (node (ref "FINGER3") (pin "4") (pinfunction "4_4") (pintype "bidirectional"))
      (node (ref "FINGER4") (pin "4") (pinfunction "4_4") (pintype "bidirectional"))
      (node (ref "FINGER5") (pin "4") (pinfunction "4_4") (pintype "bidirectional"))
      (node (ref "FINGER6") (pin "4") (pinfunction "4_4") (pintype "bidirectional"))
      (node (ref "FINGER7") (pin "4") (pinfunction "4_4") (pintype "bidirectional"))
      (node (ref "GBA_CONNECTOR") (pin "P$31") (pinfunction "I2C_SCL_P$31") (pintype "bidirectional"))
      (node (ref "INA219") (pin "5") (pinfunction "SCL_5") (pintype "bidirectional"))
      (node (ref "R5") (pin "2") (pinfunction "2_2") (pintype "passive"))
    )
    (net (code "48") (name "SDA") (class "Default")
      (node (ref "FINGER1") (pin "5") (pinfunction "5_5") (pintype "bidirectional"))
      (node (ref "FINGER2") (pin "5") (pinfunction "5_5") (pintype "bidirectional"))
      (node (ref "FINGER3") (pin "5") (pinfunction "5_5") (pintype "bidirectional"))
      (node (ref "FINGER4") (pin "5") (pinfunction "5_5") (pintype "bidirectional"))
      (node (ref "FINGER5") (pin "5") (pinfunction "5_5") (pintype "bidirectional"))
      (node (ref "FINGER6") (pin "5") (pinfunction "5_5") (pintype "bidirectional"))
      (node (ref "FINGER7") (pin "5") (pinfunction "5_5") (pintype "bidirectional"))
      (node (ref "GBA_CONNECTOR") (pin "P$30") (pinfunction "I2C_SDA_P$30") (pintype "bidirectional"))
      (node (ref "INA219") (pin "6") (pinfunction "SDA_6") (pintype "bidirectional"))
      (node (ref "R4") (pin "2") (pinfunction "2_2") (pintype "passive"))
    )
    (net (code "49") (name "SOK") (class "Default")
      (node (ref "GBA_CONNECTOR") (pin "P$5") (pinfunction "SOK_P$5") (pintype "bidirectional"))
      (node (ref "R6") (pin "2") (pinfunction "2_2") (pintype "passive"))
      (node (ref "R7") (pin "1") (pinfunction "1_1") (pintype "passive"))
    )
    (net (code "50") (name "VBAT") (class "Default")
      (node (ref "5.0V_REGULATOR") (pin "2") (pinfunction "VIN_2") (pintype "bidirectional"))
      (node (ref "C19") (pin "1") (pinfunction "P$1_1") (pintype "passive"))
      (node (ref "INA219") (pin "2") (pinfunction "VIN-_2") (pintype "bidirectional"))
      (node (ref "INA_BYPASS") (pin "1") (pinfunction "1_1") (pintype "passive"))
      (node (ref "R18") (pin "2") (pinfunction "2_2") (pintype "passive"))
      (node (ref "R20") (pin "1") (pinfunction "1_1") (pintype "passive"))
    )
    (net (code "51") (name "VLIPO") (class "Default")
      (node (ref "BATTERY") (pin "3") (pinfunction "S_3") (pintype "passive"))
      (node (ref "INA219") (pin "1") (pinfunction "VIN+_1") (pintype "bidirectional"))
      (node (ref "INA_BYPASS") (pin "2") (pinfunction "2_2") (pintype "passive"))
      (node (ref "R20") (pin "2") (pinfunction "2_2") (pintype "passive"))
    )
    (net (code "52") (name "unconnected-(3.3V_REGULATOR-NC_1-Pad8)") (class "Default")
      (node (ref "3.3V_REGULATOR") (pin "8") (pinfunction "NC_1_8") (pintype "bidirectional"))
    )
    (net (code "53") (name "unconnected-(3.3V_REGULATOR-NC_2-Pad11)") (class "Default")
      (node (ref "3.3V_REGULATOR") (pin "11") (pinfunction "NC_2_11") (pintype "bidirectional"))
    )
    (net (code "54") (name "unconnected-(3.3V_REGULATOR-NC_3-Pad12)") (class "Default")
      (node (ref "3.3V_REGULATOR") (pin "12") (pinfunction "NC_3_12") (pintype "bidirectional"))
    )
    (net (code "55") (name "unconnected-(3.3V_REGULATOR-PG-Pad10)") (class "Default")
      (node (ref "3.3V_REGULATOR") (pin "10") (pinfunction "PG_10") (pintype "bidirectional"))
    )
    (net (code "56") (name "unconnected-(3.3V_REGULATOR-SEQ-Pad9)") (class "Default")
      (node (ref "3.3V_REGULATOR") (pin "9") (pinfunction "SEQ_9") (pintype "bidirectional"))
    )
    (net (code "57") (name "unconnected-(5.0V_REGULATOR-NC_1-Pad8)") (class "Default")
      (node (ref "5.0V_REGULATOR") (pin "8") (pinfunction "NC_1_8") (pintype "bidirectional"))
    )
    (net (code "58") (name "unconnected-(5.0V_REGULATOR-NC_2-Pad11)") (class "Default")
      (node (ref "5.0V_REGULATOR") (pin "11") (pinfunction "NC_2_11") (pintype "bidirectional"))
    )
    (net (code "59") (name "unconnected-(5.0V_REGULATOR-NC_3-Pad12)") (class "Default")
      (node (ref "5.0V_REGULATOR") (pin "12") (pinfunction "NC_3_12") (pintype "bidirectional"))
    )
    (net (code "60") (name "unconnected-(5.0V_REGULATOR-SEQ-Pad9)") (class "Default")
      (node (ref "5.0V_REGULATOR") (pin "9") (pinfunction "SEQ_9") (pintype "bidirectional"))
    )
    (net (code "61") (name "unconnected-(BATTERYB-S-Pad2)") (class "Default")
      (node (ref "BATTERY") (pin "2") (pinfunction "S_2") (pintype "passive"))
    )
    (net (code "62") (name "unconnected-(SW1-O-PadA)") (class "Default")
      (node (ref "SW1") (pin "A") (pinfunction "O_A") (pintype "passive"))
    )
  )
)
